# MINI_SAM_D51_rAD1_b002.net
KiCad netlist of a schematic drawn in EAGLE
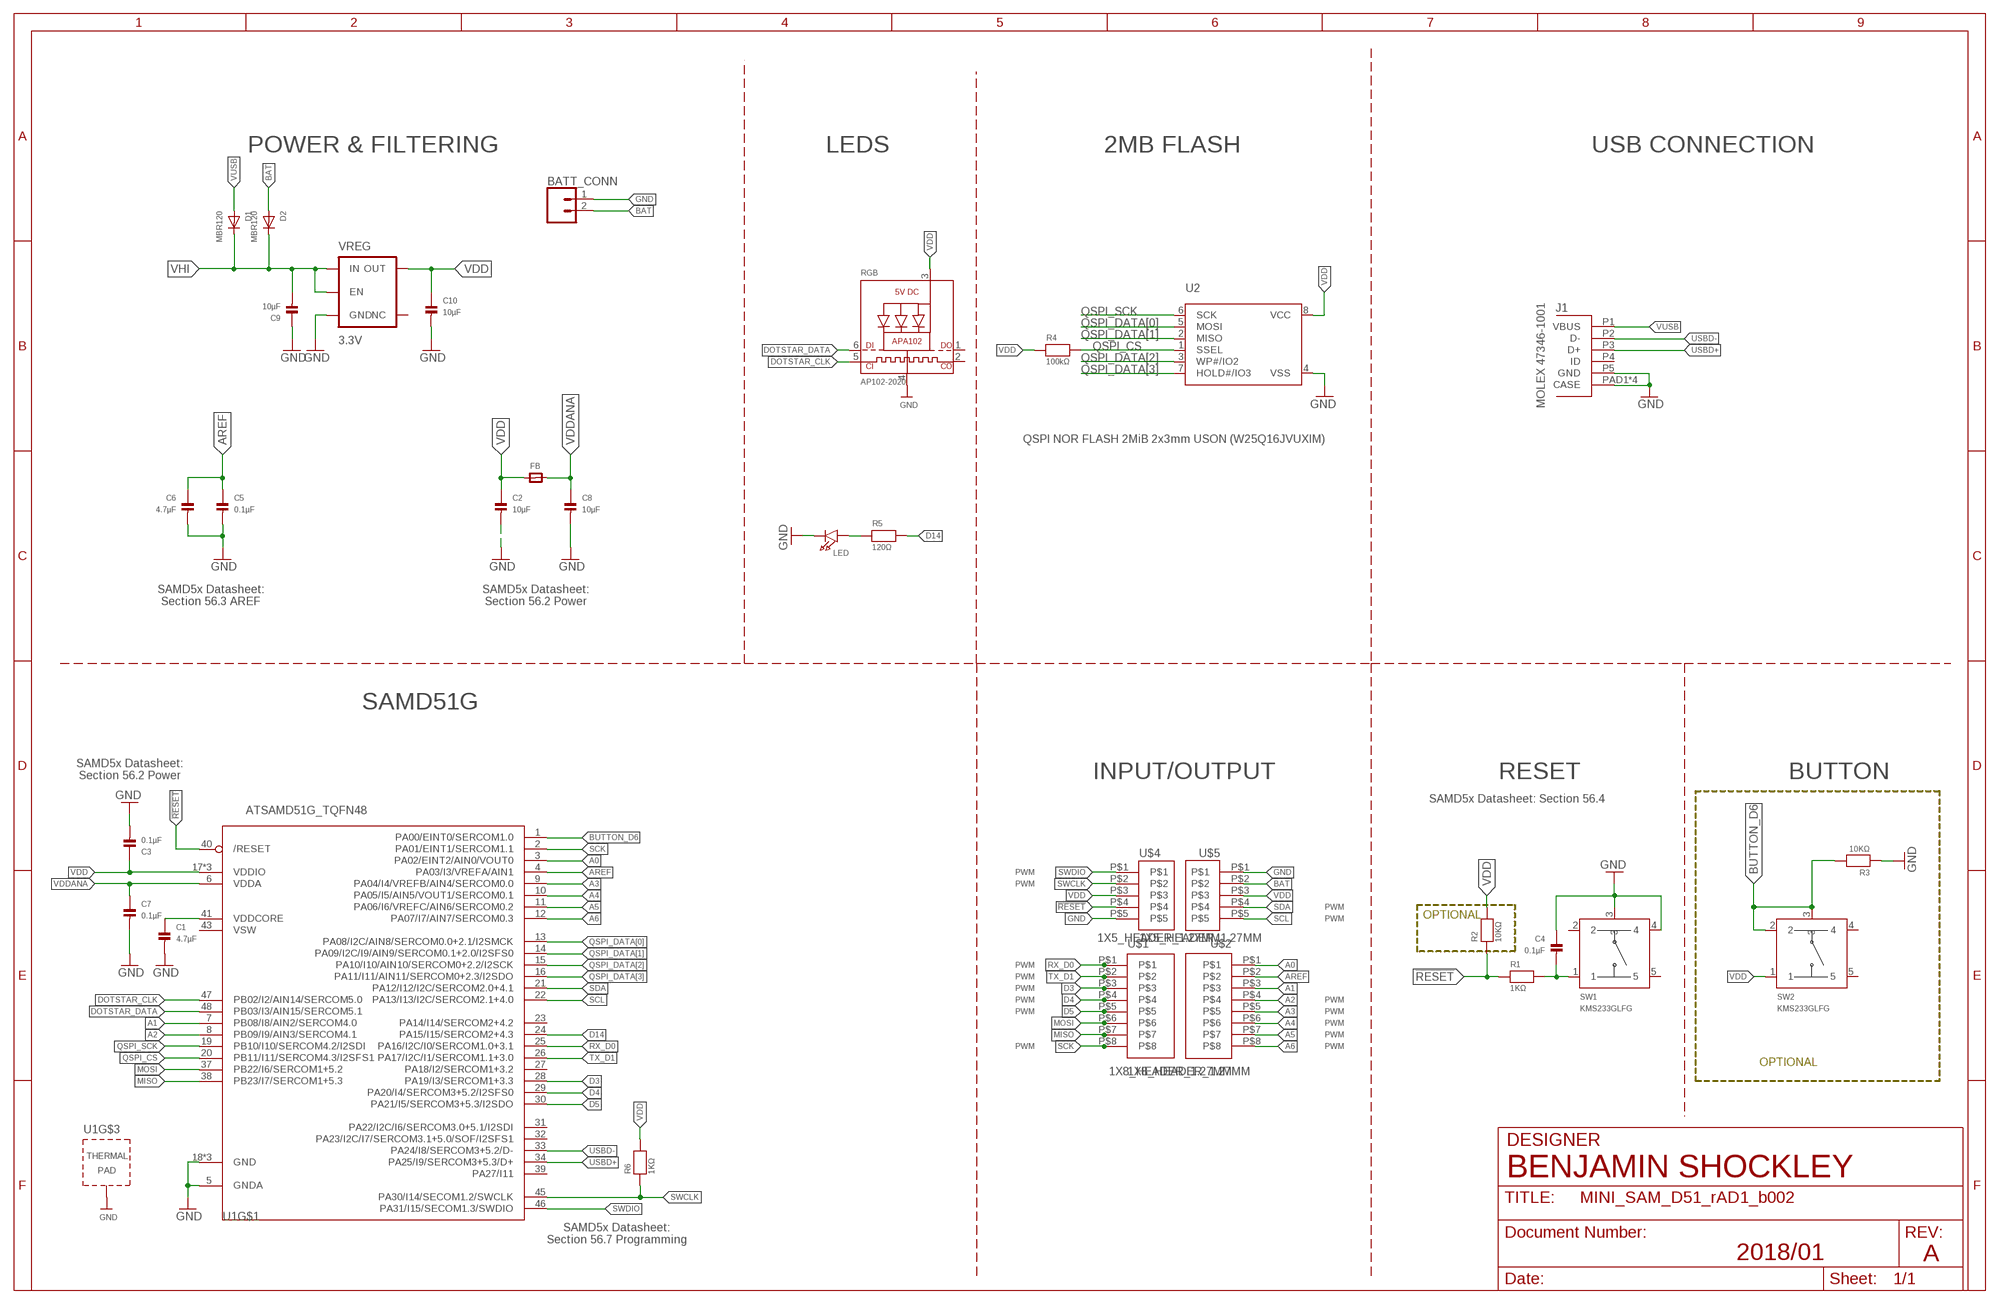
[diagram p0: schematic, sheet 1]

(export (version "E")
  (design (tool "Eeschema 10.0.6"))
  (components
    (comp (ref "BATT_CONN")
      (value "CONN_02-JST-2MM-SMT")
      (footprint "eagle-import:JST-2-SMD_NO_PASTE")
      (libsource (lib "eagle-import") (part "CONN_02-JST-2MM-SMT"))
    )
    (comp (ref "C1")
      (value "4.7µF")
      (footprint "eagle-import:0603_CAPACITOR")
      (libsource (lib "eagle-import") (part "CAP_CERAMICQUIRKY"))
    )
    (comp (ref "C2")
      (value "10µF")
      (footprint "eagle-import:0603_CAPACITOR")
      (libsource (lib "eagle-import") (part "CAP_CERAMICQUIRKY"))
    )
    (comp (ref "C3")
      (value "0.1µF")
      (footprint "eagle-import:0603_CAPACITOR")
      (libsource (lib "eagle-import") (part "CAP_CERAMICQUIRKY"))
    )
    (comp (ref "C4")
      (value "0.1µF")
      (footprint "eagle-import:0603_CAPACITOR")
      (libsource (lib "eagle-import") (part "CAP_CERAMICQUIRKY"))
    )
    (comp (ref "C5")
      (value "0.1µF")
      (footprint "eagle-import:0603_CAPACITOR")
      (libsource (lib "eagle-import") (part "CAP_CERAMICQUIRKY"))
    )
    (comp (ref "C6")
      (value "4.7µF")
      (footprint "eagle-import:0603_CAPACITOR")
      (libsource (lib "eagle-import") (part "CAP_CERAMICQUIRKY"))
    )
    (comp (ref "C7")
      (value "0.1µF")
      (footprint "eagle-import:0603_CAPACITOR")
      (libsource (lib "eagle-import") (part "CAP_CERAMICQUIRKY"))
    )
    (comp (ref "C8")
      (value "10µF")
      (footprint "eagle-import:0603_CAPACITOR")
      (libsource (lib "eagle-import") (part "CAP_CERAMICQUIRKY"))
    )
    (comp (ref "C9")
      (value "10µF")
      (footprint "eagle-import:0603_CAPACITOR")
      (libsource (lib "eagle-import") (part "CAP_CERAMICQUIRKY"))
    )
    (comp (ref "C10")
      (value "10µF")
      (footprint "eagle-import:0603_CAPACITOR")
      (libsource (lib "eagle-import") (part "CAP_CERAMICQUIRKY"))
    )
    (comp (ref "D1")
      (value "MBR120")
      (footprint "eagle-import:SOD-123FL")
      (libsource (lib "eagle-import") (part "DIODE_SOD-123FL"))
    )
    (comp (ref "D2")
      (value "MBR120")
      (footprint "eagle-import:SOD-123FL")
      (libsource (lib "eagle-import") (part "DIODE_SOD-123FL"))
    )
    (comp (ref "FB")
      (value "Impedence: 50 ohm @ 20 MHz, 220 Ohm @ 100 MHz; low DC resistance")
      (footprint "eagle-import:0603_INDUCTOR")
      (libsource (lib "eagle-import") (part "FERRITEQUIRKY"))
    )
    (comp (ref "J1")
      (value "MOLEX_47346-100147346")
      (footprint "eagle-import:MOLEX_47346-1001")
      (libsource (lib "eagle-import") (part "MOLEX_47346-100147346"))
    )
    (comp (ref "LED")
      (value "VLRK31Q1R2-GS08")
      (footprint "eagle-import:REVERSE_MOUNT_LED")
      (libsource (lib "eagle-import") (part "REVERSEMOUNTLED"))
    )
    (comp (ref "R1")
      (value "1KΩ")
      (footprint "eagle-import:0603_RESISTOR")
      (libsource (lib "eagle-import") (part "RESISTORQUIRKY"))
    )
    (comp (ref "R2")
      (value "10KΩ")
      (footprint "eagle-import:0603_RESISTOR")
      (libsource (lib "eagle-import") (part "RESISTORQUIRKY"))
    )
    (comp (ref "R3")
      (value "10KΩ")
      (footprint "eagle-import:0603_RESISTOR")
      (libsource (lib "eagle-import") (part "RESISTORQUIRKY"))
    )
    (comp (ref "R4")
      (value "100kΩ")
      (footprint "eagle-import:0603_RESISTOR")
      (libsource (lib "eagle-import") (part "RESISTORQUIRKY"))
    )
    (comp (ref "R5")
      (value "120Ω")
      (footprint "eagle-import:0603_RESISTOR")
      (libsource (lib "eagle-import") (part "RESISTORQUIRKY"))
    )
    (comp (ref "R6")
      (value "1KΩ")
      (footprint "eagle-import:0603_RESISTOR")
      (libsource (lib "eagle-import") (part "RESISTORQUIRKY"))
    )
    (comp (ref "RGB")
      (value "AP102-2020")
      (footprint "eagle-import:APA102_2020")
      (libsource (lib "eagle-import") (part "APA1022020"))
    )
    (comp (ref "SW1")
      (value "KMS233GLFG")
      (footprint "eagle-import:KMS_SWITCH")
      (libsource (lib "eagle-import") (part "KMS_SWITCHKMS"))
    )
    (comp (ref "SW2")
      (value "KMS233GLFG")
      (footprint "eagle-import:KMS_SWITCH")
      (libsource (lib "eagle-import") (part "KMS_SWITCHKMS"))
    )
    (comp (ref "U$1")
      (value "1X8_HEADER_1.27MM")
      (footprint "eagle-import:1X8_HEADER_1.27MM")
      (libsource (lib "eagle-import") (part "1X8_HEADER_1.27MM"))
    )
    (comp (ref "U$2")
      (value "1X8_HEADER_1.27MM")
      (footprint "eagle-import:1X8_HEADER_1.27MM")
      (libsource (lib "eagle-import") (part "1X8_HEADER_1.27MM"))
    )
    (comp (ref "U$4")
      (value "1X5_HEADER_1.27MM")
      (footprint "eagle-import:1X5_HEADER_1.27MM")
      (libsource (lib "eagle-import") (part "1X5_HEADER_1.27MM"))
    )
    (comp (ref "U$5")
      (value "1X5_HEADER_1.27MM")
      (footprint "eagle-import:1X5_HEADER_1.27MM")
      (libsource (lib "eagle-import") (part "1X5_HEADER_1.27MM"))
    )
    (comp (ref "U1")
      (value "ATSAMD51G_TQFN48")
      (footprint "eagle-import:TQFN48_7MM")
      (libsource (lib "eagle-import") (part "ATSAMD51G_TQFN48"))
    )
    (comp (ref "U2")
      (value "QSPI NOR FLASH 2MiB 2x3mm USON (W25Q16JVUXIM)")
      (footprint "eagle-import:USON8")
      (libsource (lib "eagle-import") (part "SPIFLASH_8PINUX"))
    )
    (comp (ref "VREG")
      (value "3.3V")
      (footprint "eagle-import:SOT23-5")
      (libsource (lib "eagle-import") (part "V_REG_AP2112K-3.3V"))
    )
  )
  (nets
    (net (code "1") (name "/VSW") (class "Default")
      (node (ref "U1") (pin "43") (pinfunction "VSW_43") (pintype "power_in"))
    )
    (net (code "2") (name "/~{RESET}") (class "Default")
      (node (ref "R1") (pin "1") (pinfunction "1_1") (pintype "passive"))
      (node (ref "R2") (pin "1") (pinfunction "1_1") (pintype "passive"))
      (node (ref "U$4") (pin "P$4") (pinfunction "P$4_P$4") (pintype "bidirectional"))
      (node (ref "U1") (pin "40") (pinfunction "/RESET_40") (pintype "bidirectional"))
    )
    (net (code "3") (name "A0") (class "Default")
      (node (ref "U$2") (pin "P$1") (pinfunction "P$1_P$1") (pintype "bidirectional"))
      (node (ref "U1") (pin "3") (pinfunction "PA02/EINT2/AIN0/VOUT0_3") (pintype "bidirectional"))
    )
    (net (code "4") (name "A1") (class "Default")
      (node (ref "U$2") (pin "P$3") (pinfunction "P$3_P$3") (pintype "bidirectional"))
      (node (ref "U1") (pin "7") (pinfunction "PB08/I8/AIN2/SERCOM4.0_7") (pintype "bidirectional"))
    )
    (net (code "5") (name "A2") (class "Default")
      (node (ref "U$2") (pin "P$4") (pinfunction "P$4_P$4") (pintype "bidirectional"))
      (node (ref "U1") (pin "8") (pinfunction "PB09/I9/AIN3/SERCOM4.1_8") (pintype "bidirectional"))
    )
    (net (code "6") (name "A3") (class "Default")
      (node (ref "U$2") (pin "P$5") (pinfunction "P$5_P$5") (pintype "bidirectional"))
      (node (ref "U1") (pin "9") (pinfunction "PA04/I4/VREFB/AIN4/SERCOM0.0_9") (pintype "bidirectional"))
    )
    (net (code "7") (name "A4") (class "Default")
      (node (ref "U$2") (pin "P$6") (pinfunction "P$6_P$6") (pintype "bidirectional"))
      (node (ref "U1") (pin "10") (pinfunction "PA05/I5/AIN5/VOUT1/SERCOM0.1_10") (pintype "bidirectional"))
    )
    (net (code "8") (name "A5") (class "Default")
      (node (ref "U$2") (pin "P$7") (pinfunction "P$7_P$7") (pintype "bidirectional"))
      (node (ref "U1") (pin "11") (pinfunction "PA06/I6/VREFC/AIN6/SERCOM0.2_11") (pintype "bidirectional"))
    )
    (net (code "9") (name "A6") (class "Default")
      (node (ref "U$2") (pin "P$8") (pinfunction "P$8_P$8") (pintype "bidirectional"))
      (node (ref "U1") (pin "12") (pinfunction "PA07/I7/AIN7/SERCOM0.3_12") (pintype "bidirectional"))
    )
    (net (code "10") (name "AREF") (class "Default")
      (node (ref "C5") (pin "1") (pinfunction "P$1_1") (pintype "passive"))
      (node (ref "C6") (pin "1") (pinfunction "P$1_1") (pintype "passive"))
      (node (ref "U$2") (pin "P$2") (pinfunction "P$2_P$2") (pintype "bidirectional"))
      (node (ref "U1") (pin "4") (pinfunction "PA03/I3/VREFA/AIN1_4") (pintype "bidirectional"))
    )
    (net (code "11") (name "BAT") (class "Default")
      (node (ref "BATT_CONN") (pin "2") (pinfunction "1_2") (pintype "passive"))
      (node (ref "D2") (pin "A") (pinfunction "A_A") (pintype "passive"))
      (node (ref "U$5") (pin "P$2") (pinfunction "P$2_P$2") (pintype "bidirectional"))
    )
    (net (code "12") (name "BUTTON_D6") (class "Default")
      (node (ref "R3") (pin "2") (pinfunction "2_2") (pintype "passive"))
      (node (ref "SW2") (pin "2") (pinfunction "2_2") (pintype "bidirectional"))
      (node (ref "SW2") (pin "3") (pinfunction "3_3") (pintype "bidirectional"))
      (node (ref "U1") (pin "1") (pinfunction "PA00/EINT0/SERCOM1.0_1") (pintype "bidirectional"))
    )
    (net (code "13") (name "D3") (class "Default")
      (node (ref "U$1") (pin "P$3") (pinfunction "P$3_P$3") (pintype "bidirectional"))
      (node (ref "U1") (pin "28") (pinfunction "PA19/I3/SERCOM1+3.3_28") (pintype "bidirectional"))
    )
    (net (code "14") (name "D4") (class "Default")
      (node (ref "U$1") (pin "P$4") (pinfunction "P$4_P$4") (pintype "bidirectional"))
      (node (ref "U1") (pin "29") (pinfunction "PA20/I4/SERCOM3+5.2/I2SFS0_29") (pintype "bidirectional"))
    )
    (net (code "15") (name "D5") (class "Default")
      (node (ref "U$1") (pin "P$5") (pinfunction "P$5_P$5") (pintype "bidirectional"))
      (node (ref "U1") (pin "30") (pinfunction "PA21/I5/SERCOM3+5.3/I2SDO_30") (pintype "bidirectional"))
    )
    (net (code "16") (name "D14") (class "Default")
      (node (ref "R5") (pin "2") (pinfunction "2_2") (pintype "passive"))
      (node (ref "U1") (pin "24") (pinfunction "PA15/I15/SERCOM2+4.3_24") (pintype "bidirectional"))
    )
    (net (code "17") (name "DOTSTAR_CLK") (class "Default")
      (node (ref "RGB") (pin "5") (pinfunction "CKI_5") (pintype "input"))
      (node (ref "U1") (pin "47") (pinfunction "PB02/I2/AIN14/SERCOM5.0_47") (pintype "bidirectional"))
    )
    (net (code "18") (name "DOTSTAR_DATA") (class "Default")
      (node (ref "RGB") (pin "6") (pinfunction "DI_6") (pintype "input"))
      (node (ref "U1") (pin "48") (pinfunction "PB03/I3/AIN15/SERCOM5.1_48") (pintype "bidirectional"))
    )
    (net (code "19") (name "GND") (class "Default")
      (node (ref "BATT_CONN") (pin "1") (pinfunction "2_1") (pintype "passive"))
      (node (ref "C1") (pin "2") (pinfunction "P$2_2") (pintype "passive"))
      (node (ref "C10") (pin "2") (pinfunction "P$2_2") (pintype "passive"))
      (node (ref "C2") (pin "2") (pinfunction "P$2_2") (pintype "passive"))
      (node (ref "C3") (pin "2") (pinfunction "P$2_2") (pintype "passive"))
      (node (ref "C4") (pin "1") (pinfunction "P$1_1") (pintype "passive"))
      (node (ref "C5") (pin "2") (pinfunction "P$2_2") (pintype "passive"))
      (node (ref "C6") (pin "2") (pinfunction "P$2_2") (pintype "passive"))
      (node (ref "C7") (pin "2") (pinfunction "P$2_2") (pintype "passive"))
      (node (ref "C8") (pin "2") (pinfunction "P$2_2") (pintype "passive"))
      (node (ref "C9") (pin "1") (pinfunction "P$1_1") (pintype "passive"))
      (node (ref "J1") (pin "P5") (pinfunction "GND_P5") (pintype "power_in"))
      (node (ref "J1") (pin "PAD1") (pinfunction "CASE_PAD1") (pintype "bidirectional"))
      (node (ref "J1") (pin "PAD2") (pinfunction "CASE_PAD2") (pintype "bidirectional"))
      (node (ref "J1") (pin "PAD3") (pinfunction "CASE_PAD3") (pintype "bidirectional"))
      (node (ref "J1") (pin "PAD4") (pinfunction "CASE_PAD4") (pintype "bidirectional"))
      (node (ref "LED") (pin "C") (pinfunction "C_C") (pintype "passive"))
      (node (ref "R3") (pin "1") (pinfunction "1_1") (pintype "passive"))
      (node (ref "RGB") (pin "4") (pinfunction "GND_4") (pintype "power_in"))
      (node (ref "SW1") (pin "3") (pinfunction "3_3") (pintype "bidirectional"))
      (node (ref "SW1") (pin "4") (pinfunction "4_4") (pintype "bidirectional"))
      (node (ref "U$4") (pin "P$5") (pinfunction "P$5_P$5") (pintype "bidirectional"))
      (node (ref "U$5") (pin "P$1") (pinfunction "P$1_P$1") (pintype "bidirectional"))
      (node (ref "U1") (pin "18") (pinfunction "GND_18") (pintype "power_in"))
      (node (ref "U1") (pin "35") (pinfunction "GND_35") (pintype "power_in"))
      (node (ref "U1") (pin "42") (pinfunction "GND_42") (pintype "power_in"))
      (node (ref "U1") (pin "5") (pinfunction "GNDA_5") (pintype "power_in"))
      (node (ref "U1") (pin "THERMAL") (pinfunction "TP_THERMAL") (pintype "power_in"))
      (node (ref "U2") (pin "4") (pinfunction "VSS_4") (pintype "bidirectional"))
      (node (ref "VREG") (pin "2") (pinfunction "GND_2") (pintype "input"))
    )
    (net (code "20") (name "MISO") (class "Default")
      (node (ref "U$1") (pin "P$7") (pinfunction "P$7_P$7") (pintype "bidirectional"))
      (node (ref "U1") (pin "38") (pinfunction "PB23/I7/SERCOM1+5.3_38") (pintype "bidirectional"))
    )
    (net (code "21") (name "MOSI") (class "Default")
      (node (ref "U$1") (pin "P$6") (pinfunction "P$6_P$6") (pintype "bidirectional"))
      (node (ref "U1") (pin "37") (pinfunction "PB22/I6/SERCOM1+5.2_37") (pintype "bidirectional"))
    )
    (net (code "22") (name "Net-(C1-P$1)") (class "Default")
      (node (ref "C1") (pin "1") (pinfunction "P$1_1") (pintype "passive"))
      (node (ref "U1") (pin "41") (pinfunction "VDDCORE_41") (pintype "power_in"))
    )
    (net (code "23") (name "Net-(C4-P$2)") (class "Default")
      (node (ref "C4") (pin "2") (pinfunction "P$2_2") (pintype "passive"))
      (node (ref "R1") (pin "2") (pinfunction "2_2") (pintype "passive"))
      (node (ref "SW1") (pin "1") (pinfunction "1_1") (pintype "bidirectional"))
    )
    (net (code "24") (name "Net-(LED-PadA)") (class "Default")
      (node (ref "LED") (pin "A") (pinfunction "A_A") (pintype "passive"))
      (node (ref "R5") (pin "1") (pinfunction "1_1") (pintype "passive"))
    )
    (net (code "25") (name "QSPI_CS") (class "Default")
      (node (ref "R4") (pin "2") (pinfunction "2_2") (pintype "passive"))
      (node (ref "U1") (pin "20") (pinfunction "PB11/I11/SERCOM4.3/I2SFS1_20") (pintype "bidirectional"))
      (node (ref "U2") (pin "1") (pinfunction "SSEL_1") (pintype "bidirectional"))
    )
    (net (code "26") (name "QSPI_DATA[0]") (class "Default")
      (node (ref "U1") (pin "13") (pinfunction "PA08/I2C/AIN8/SERCOM0.0+2.1/I2SMCK_13") (pintype "bidirectional"))
      (node (ref "U2") (pin "5") (pinfunction "MOSI_5") (pintype "bidirectional"))
    )
    (net (code "27") (name "QSPI_DATA[1]") (class "Default")
      (node (ref "U1") (pin "14") (pinfunction "PA09/I2C/I9/AIN9/SERCOM0.1+2.0/I2SFS0_14") (pintype "bidirectional"))
      (node (ref "U2") (pin "2") (pinfunction "MISO_2") (pintype "bidirectional"))
    )
    (net (code "28") (name "QSPI_DATA[2]") (class "Default")
      (node (ref "U1") (pin "15") (pinfunction "PA10/I10/AIN10/SERCOM0+2.2/I2SCK_15") (pintype "bidirectional"))
      (node (ref "U2") (pin "3") (pinfunction "WP#/IO2_3") (pintype "bidirectional"))
    )
    (net (code "29") (name "QSPI_DATA[3]") (class "Default")
      (node (ref "U1") (pin "16") (pinfunction "PA11/I11/AIN11/SERCOM0+2.3/I2SDO_16") (pintype "bidirectional"))
      (node (ref "U2") (pin "7") (pinfunction "HOLD#/IO3_7") (pintype "bidirectional"))
    )
    (net (code "30") (name "QSPI_SCK") (class "Default")
      (node (ref "U1") (pin "19") (pinfunction "PB10/I10/SERCOM4.2/I2SDI_19") (pintype "bidirectional"))
      (node (ref "U2") (pin "6") (pinfunction "SCK_6") (pintype "bidirectional"))
    )
    (net (code "31") (name "RX_D0") (class "Default")
      (node (ref "U$1") (pin "P$1") (pinfunction "P$1_P$1") (pintype "bidirectional"))
      (node (ref "U1") (pin "25") (pinfunction "PA16/I2C/I0/SERCOM1.0+3.1_25") (pintype "bidirectional"))
    )
    (net (code "32") (name "SCK") (class "Default")
      (node (ref "U$1") (pin "P$8") (pinfunction "P$8_P$8") (pintype "bidirectional"))
      (node (ref "U1") (pin "2") (pinfunction "PA01/EINT1/SERCOM1.1_2") (pintype "bidirectional"))
    )
    (net (code "33") (name "SCL") (class "Default")
      (node (ref "U$5") (pin "P$5") (pinfunction "P$5_P$5") (pintype "bidirectional"))
      (node (ref "U1") (pin "22") (pinfunction "PA13/I13/I2C/SERCOM2.1+4.0_22") (pintype "bidirectional"))
    )
    (net (code "34") (name "SDA") (class "Default")
      (node (ref "U$5") (pin "P$4") (pinfunction "P$4_P$4") (pintype "bidirectional"))
      (node (ref "U1") (pin "21") (pinfunction "PA12/I12/I2C/SERCOM2.0+4.1_21") (pintype "bidirectional"))
    )
    (net (code "35") (name "SWCLK") (class "Default")
      (node (ref "R6") (pin "1") (pinfunction "1_1") (pintype "passive"))
      (node (ref "U$4") (pin "P$2") (pinfunction "P$2_P$2") (pintype "bidirectional"))
      (node (ref "U1") (pin "45") (pinfunction "PA30/I14/SECOM1.2/SWCLK_45") (pintype "bidirectional"))
    )
    (net (code "36") (name "SWDIO") (class "Default")
      (node (ref "U$4") (pin "P$1") (pinfunction "P$1_P$1") (pintype "bidirectional"))
      (node (ref "U1") (pin "46") (pinfunction "PA31/I15/SECOM1.3/SWDIO_46") (pintype "bidirectional"))
    )
    (net (code "37") (name "TX_D1") (class "Default")
      (node (ref "U$1") (pin "P$2") (pinfunction "P$2_P$2") (pintype "bidirectional"))
      (node (ref "U1") (pin "26") (pinfunction "PA17/I2C/I1/SERCOM1.1+3.0_26") (pintype "bidirectional"))
    )
    (net (code "38") (name "USBD+") (class "Default")
      (node (ref "J1") (pin "P3") (pinfunction "D+_P3") (pintype "bidirectional"))
      (node (ref "U1") (pin "34") (pinfunction "PA25/I9/SERCOM3+5.3/D+_34") (pintype "bidirectional"))
    )
    (net (code "39") (name "USBD-") (class "Default")
      (node (ref "J1") (pin "P2") (pinfunction "D-_P2") (pintype "bidirectional"))
      (node (ref "U1") (pin "33") (pinfunction "PA24/I8/SERCOM3+5.2/D-_33") (pintype "bidirectional"))
    )
    (net (code "40") (name "VDD") (class "Default")
      (node (ref "C10") (pin "1") (pinfunction "P$1_1") (pintype "passive"))
      (node (ref "C2") (pin "1") (pinfunction "P$1_1") (pintype "passive"))
      (node (ref "C3") (pin "1") (pinfunction "P$1_1") (pintype "passive"))
      (node (ref "FB") (pin "1") (pinfunction "P$1_1") (pintype "passive"))
      (node (ref "R2") (pin "2") (pinfunction "2_2") (pintype "passive"))
      (node (ref "R4") (pin "1") (pinfunction "1_1") (pintype "passive"))
      (node (ref "R6") (pin "2") (pinfunction "2_2") (pintype "passive"))
      (node (ref "RGB") (pin "3") (pinfunction "VDD_3") (pintype "power_in"))
      (node (ref "SW2") (pin "1") (pinfunction "1_1") (pintype "bidirectional"))
      (node (ref "U$4") (pin "P$3") (pinfunction "P$3_P$3") (pintype "bidirectional"))
      (node (ref "U$5") (pin "P$3") (pinfunction "P$3_P$3") (pintype "bidirectional"))
      (node (ref "U1") (pin "17") (pinfunction "VDDIO_17") (pintype "power_in"))
      (node (ref "U1") (pin "36") (pinfunction "VDDIO_36") (pintype "power_in"))
      (node (ref "U1") (pin "44") (pinfunction "VDDIO_44") (pintype "power_in"))
      (node (ref "U2") (pin "8") (pinfunction "VCC_8") (pintype "bidirectional"))
      (node (ref "VREG") (pin "5") (pinfunction "OUT_5") (pintype "passive"))
    )
    (net (code "41") (name "VDDANA") (class "Default")
      (node (ref "C7") (pin "1") (pinfunction "P$1_1") (pintype "passive"))
      (node (ref "C8") (pin "1") (pinfunction "P$1_1") (pintype "passive"))
      (node (ref "FB") (pin "2") (pinfunction "P$2_2") (pintype "passive"))
      (node (ref "U1") (pin "6") (pinfunction "VDDA_6") (pintype "power_in"))
    )
    (net (code "42") (name "VHI") (class "Default")
      (node (ref "C9") (pin "2") (pinfunction "P$2_2") (pintype "passive"))
      (node (ref "D1") (pin "C") (pinfunction "C_C") (pintype "passive"))
      (node (ref "D2") (pin "C") (pinfunction "C_C") (pintype "passive"))
      (node (ref "VREG") (pin "1") (pinfunction "IN_1") (pintype "input"))
      (node (ref "VREG") (pin "3") (pinfunction "EN_3") (pintype "input"))
    )
    (net (code "43") (name "VUSB") (class "Default")
      (node (ref "D1") (pin "A") (pinfunction "A_A") (pintype "passive"))
      (node (ref "J1") (pin "P1") (pinfunction "VBUS_P1") (pintype "power_in"))
    )
    (net (code "44") (name "unconnected-(J1-ID-PadP4)") (class "Default")
      (node (ref "J1") (pin "P4") (pinfunction "ID_P4") (pintype "bidirectional"))
    )
    (net (code "45") (name "unconnected-(RGB-CKO-Pad2)") (class "Default")
      (node (ref "RGB") (pin "2") (pinfunction "CKO_2") (pintype "output"))
    )
    (net (code "46") (name "unconnected-(RGB-DO-Pad1)") (class "Default")
      (node (ref "RGB") (pin "1") (pinfunction "DO_1") (pintype "output"))
    )
    (net (code "47") (name "unconnected-(SW1-Pad2)") (class "Default")
      (node (ref "SW1") (pin "2") (pinfunction "2_2") (pintype "bidirectional"))
    )
    (net (code "48") (name "unconnected-(SW1-Pad5)") (class "Default")
      (node (ref "SW1") (pin "5") (pinfunction "5_5") (pintype "bidirectional"))
    )
    (net (code "49") (name "unconnected-(SW2-Pad4)") (class "Default")
      (node (ref "SW2") (pin "4") (pinfunction "4_4") (pintype "bidirectional"))
    )
    (net (code "50") (name "unconnected-(SW2-Pad5)") (class "Default")
      (node (ref "SW2") (pin "5") (pinfunction "5_5") (pintype "bidirectional"))
    )
    (net (code "51") (name "unconnected-(U1A-PA14{slash}I14{slash}SERCOM2+4.2-Pad23)") (class "Default")
      (node (ref "U1") (pin "23") (pinfunction "PA14/I14/SERCOM2+4.2_23") (pintype "bidirectional"))
    )
    (net (code "52") (name "unconnected-(U1A-PA18{slash}I2{slash}SERCOM1+3.2-Pad27)") (class "Default")
      (node (ref "U1") (pin "27") (pinfunction "PA18/I2/SERCOM1+3.2_27") (pintype "bidirectional"))
    )
    (net (code "53") (name "unconnected-(U1A-PA22{slash}I2C{slash}I6{slash}SERCOM3.0+5.1{slash}I2SDI-Pad31)") (class "Default")
      (node (ref "U1") (pin "31") (pinfunction "PA22/I2C/I6/SERCOM3.0+5.1/I2SDI_31") (pintype "bidirectional"))
    )
    (net (code "54") (name "unconnected-(U1A-PA23{slash}I2C{slash}I7{slash}SERCOM3.1+5.0{slash}SOF{slash}I2SFS1-Pad32)") (class "Default")
      (node (ref "U1") (pin "32") (pinfunction "PA23/I2C/I7/SERCOM3.1+5.0/SOF/I2SFS1_32") (pintype "bidirectional"))
    )
    (net (code "55") (name "unconnected-(U1A-PA27{slash}I11-Pad39)") (class "Default")
      (node (ref "U1") (pin "39") (pinfunction "PA27/I11_39") (pintype "bidirectional"))
    )
    (net (code "56") (name "unconnected-(VREG-NC-Pad4)") (class "Default")
      (node (ref "VREG") (pin "4") (pinfunction "NC_4") (pintype "input"))
    )
  )
)
